# 04-AD9546_Outputs.net
KiCad netlist of a schematic drawn in Altium Designer
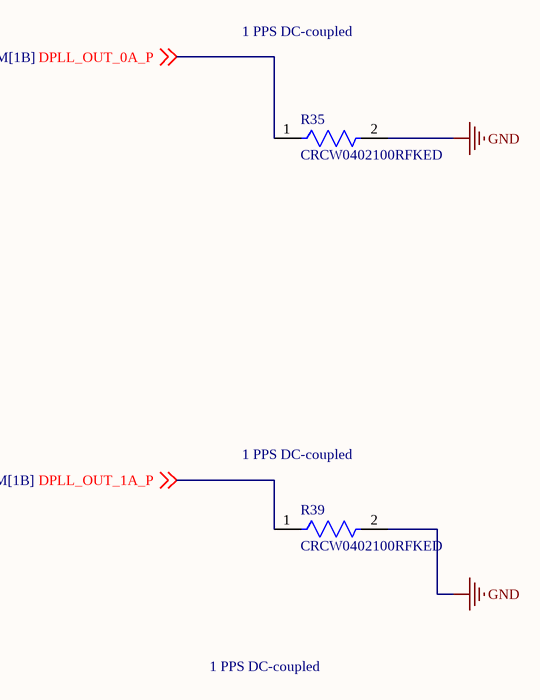
[diagram p0: 04-AD9546_Outputs.SchDoc]

(export (version "E")
  (design (tool "Eeschema 10.0.6"))
  (components
    (comp (ref "R35")
      (value "CRCW0402100RFKED")
      (footprint "FP-CRCW0402-e3-IPC_C")
      (description "RES Thick Film, 100Ω, 1%, 0.063W, 100ppm/°C, 0402")
      (fields (field (name "TOLERANCE") "1%"))
      (libsource (lib "Altium Content Vault") (part "1029c3af85768c4190bb7ad29bc67b5"))
    )
    (comp (ref "R39")
      (value "CRCW0402100RFKED")
      (footprint "FP-CRCW0402-e3-IPC_C")
      (description "RES Thick Film, 100Ω, 1%, 0.063W, 100ppm/°C, 0402")
      (fields (field (name "TOLERANCE") "1%"))
      (libsource (lib "Altium Content Vault") (part "1029c3af85768c4190bb7ad29bc67b5"))
    )
  )
  (nets
    (net (code "1") (name "DPLL_OUT_0A_P") (class "Default")
      (node (ref "R35") (pin "1") (pinfunction "1_1") (pintype "passive"))
    )
    (net (code "2") (name "DPLL_OUT_1A_P") (class "Default")
      (node (ref "R39") (pin "1") (pinfunction "1_1") (pintype "passive"))
    )
    (net (code "3") (name "GND") (class "Default")
      (node (ref "R35") (pin "2") (pinfunction "2_2") (pintype "passive"))
      (node (ref "R39") (pin "2") (pinfunction "2_2") (pintype "passive"))
    )
  )
)
